# MoteinoM0CAM-M8.net
KiCad netlist of a schematic drawn in EAGLE
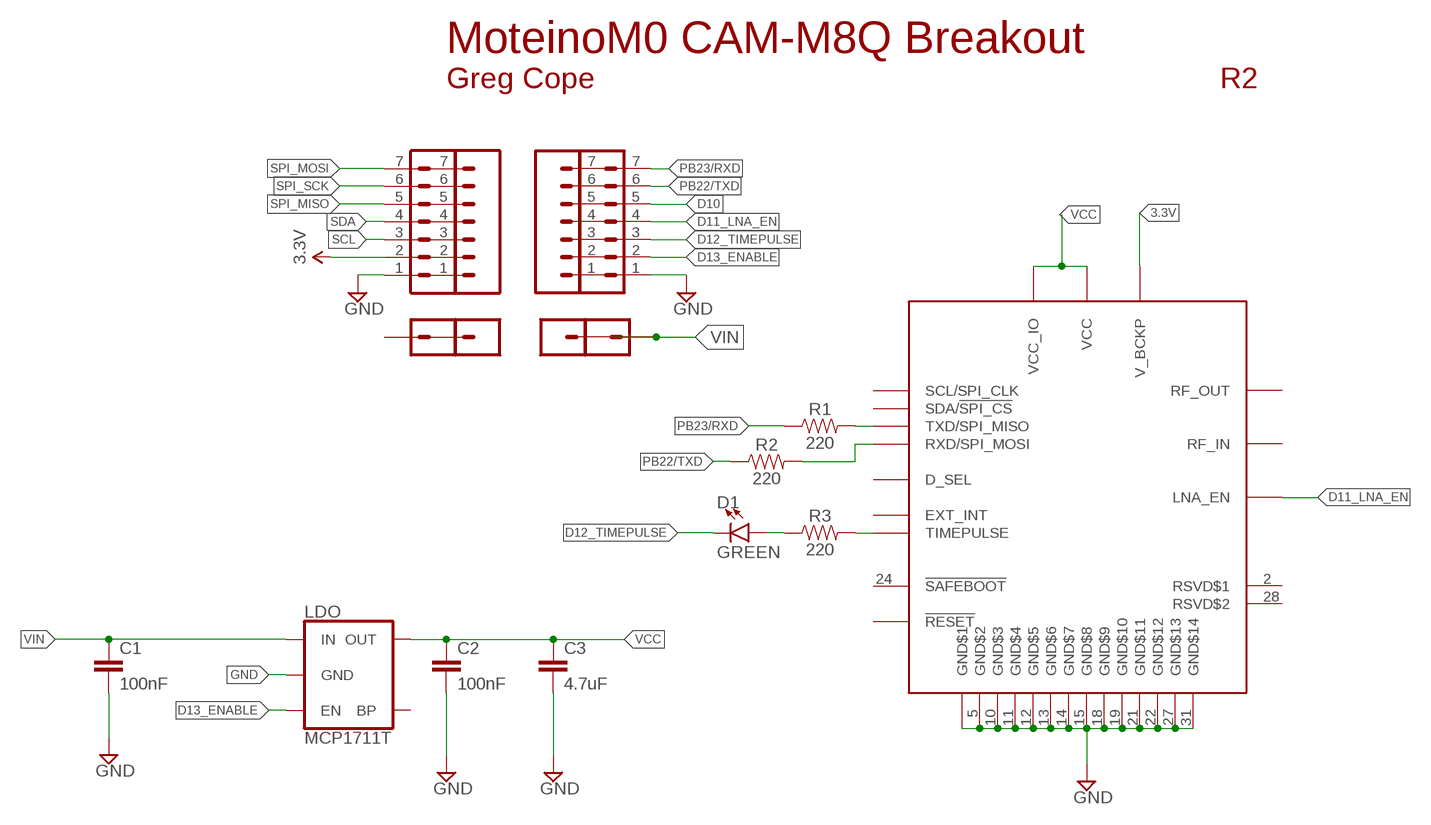
[diagram p0: schematic, sheet 1]

(export (version "E")
  (design (tool "Eeschema 10.0.6"))
  (components
    (comp (ref "C1")
      (value "100nF")
      (footprint "eagle-import:0603")
      (libsource (lib "eagle-import") (part "0.1UF-0603-25V-5%"))
    )
    (comp (ref "C2")
      (value "100nF")
      (footprint "eagle-import:0603")
      (libsource (lib "eagle-import") (part "0.1UF-0603-25V-5%"))
    )
    (comp (ref "C3")
      (value "4.7uF")
      (footprint "eagle-import:0603")
      (libsource (lib "eagle-import") (part "4.7UF0603"))
    )
    (comp (ref "D1")
      (value "GREEN")
      (footprint "eagle-import:LED-0603")
      (libsource (lib "eagle-import") (part "LED-GREEN0603"))
    )
    (comp (ref "J1")
      (value "CONN_01")
      (footprint "eagle-import:1X01")
      (libsource (lib "eagle-import") (part "CONN_01"))
    )
    (comp (ref "J2")
      (value "CONN_01")
      (footprint "eagle-import:1X01")
      (libsource (lib "eagle-import") (part "CONN_01"))
    )
    (comp (ref "J3")
      (value "CONN_01")
      (footprint "eagle-import:1X01")
      (libsource (lib "eagle-import") (part "CONN_01"))
    )
    (comp (ref "J4")
      (value "CONN_01")
      (footprint "eagle-import:1X01")
      (libsource (lib "eagle-import") (part "CONN_01"))
    )
    (comp (ref "LDO")
      (value "MCP1711T")
      (footprint "eagle-import:SOT23-5")
      (libsource (lib "eagle-import") (part "V_REG_SPX3819-SOT23-5"))
    )
    (comp (ref "R1")
      (value "220")
      (footprint "eagle-import:0603")
      (libsource (lib "eagle-import") (part "220OHM-0603-1/10W-1%"))
    )
    (comp (ref "R2")
      (value "220")
      (footprint "eagle-import:0603")
      (libsource (lib "eagle-import") (part "220OHM-0603-1/10W-1%"))
    )
    (comp (ref "R3")
      (value "220")
      (footprint "eagle-import:0603")
      (libsource (lib "eagle-import") (part "220OHM-0603-1/10W-1%"))
    )
    (comp (ref "U$1")
      (value "CAM-M8")
      (footprint "eagle-import:CAM-M8")
      (libsource (lib "eagle-import") (part "CAM-M8"))
    )
    (comp (ref "U$4")
      (value "HDR_7PINNS_THINRINGS")
      (footprint "eagle-import:1X07_NS_THINRINGS")
      (libsource (lib "eagle-import") (part "HDR_7PINNS_THINRINGS"))
    )
    (comp (ref "U$10")
      (value "HDR_7PINNS_THINRINGS")
      (footprint "eagle-import:1X07_NS_THINRINGS")
      (libsource (lib "eagle-import") (part "HDR_7PINNS_THINRINGS"))
    )
    (comp (ref "U$17")
      (value "HDR_7PINHH")
      (footprint "eagle-import:1X07_NS_THINRINGS_HH")
      (libsource (lib "eagle-import") (part "HDR_7PINHH"))
    )
    (comp (ref "U$18")
      (value "HDR_7PINHH")
      (footprint "eagle-import:1X07_NS_THINRINGS_HH")
      (libsource (lib "eagle-import") (part "HDR_7PINHH"))
    )
  )
  (nets
    (net (code "1") (name "3.3V") (class "Default")
      (node (ref "U$1") (pin "8") (pinfunction "V_BCKP_8") (pintype "power_in"))
      (node (ref "U$18") (pin "2") (pinfunction "2_2") (pintype "passive"))
    )
    (net (code "2") (name "D10") (class "Default")
      (node (ref "U$17") (pin "5") (pinfunction "5_5") (pintype "passive"))
    )
    (net (code "3") (name "D11_LNA_EN") (class "Default")
      (node (ref "U$1") (pin "30") (pinfunction "LNA_EN_30") (pintype "output"))
      (node (ref "U$17") (pin "4") (pinfunction "4_4") (pintype "passive"))
    )
    (net (code "4") (name "D12_TIMEPULSE") (class "Default")
      (node (ref "D1") (pin "C") (pinfunction "C_C") (pintype "passive"))
      (node (ref "U$17") (pin "3") (pinfunction "3_3") (pintype "passive"))
    )
    (net (code "5") (name "D13_ENABLE") (class "Default")
      (node (ref "LDO") (pin "3") (pinfunction "EN_3") (pintype "input"))
      (node (ref "U$17") (pin "2") (pinfunction "2_2") (pintype "passive"))
    )
    (net (code "6") (name "GND") (class "Default")
      (node (ref "C1") (pin "2") (pinfunction "2_2") (pintype "passive"))
      (node (ref "C2") (pin "2") (pinfunction "2_2") (pintype "passive"))
      (node (ref "C3") (pin "2") (pinfunction "2_2") (pintype "passive"))
      (node (ref "LDO") (pin "2") (pinfunction "GND_2") (pintype "input"))
      (node (ref "U$1") (pin "10") (pinfunction "GND$3_10") (pintype "power_in"))
      (node (ref "U$1") (pin "11") (pinfunction "GND$4_11") (pintype "power_in"))
      (node (ref "U$1") (pin "12") (pinfunction "GND$5_12") (pintype "power_in"))
      (node (ref "U$1") (pin "13") (pinfunction "GND$6_13") (pintype "power_in"))
      (node (ref "U$1") (pin "14") (pinfunction "GND$7_14") (pintype "power_in"))
      (node (ref "U$1") (pin "15") (pinfunction "GND$8_15") (pintype "power_in"))
      (node (ref "U$1") (pin "18") (pinfunction "GND$9_18") (pintype "power_in"))
      (node (ref "U$1") (pin "19") (pinfunction "GND$10_19") (pintype "power_in"))
      (node (ref "U$1") (pin "21") (pinfunction "GND$11_21") (pintype "power_in"))
      (node (ref "U$1") (pin "22") (pinfunction "GND$12_22") (pintype "power_in"))
      (node (ref "U$1") (pin "27") (pinfunction "GND$13_27") (pintype "power_in"))
      (node (ref "U$1") (pin "31") (pinfunction "GND$14_31") (pintype "power_in"))
      (node (ref "U$1") (pin "4") (pinfunction "GND$1_4") (pintype "power_in"))
      (node (ref "U$1") (pin "5") (pinfunction "GND$2_5") (pintype "power_in"))
      (node (ref "U$17") (pin "1") (pinfunction "1_1") (pintype "passive"))
      (node (ref "U$18") (pin "1") (pinfunction "1_1") (pintype "passive"))
    )
    (net (code "7") (name "Net-(D1-PadA)") (class "Default")
      (node (ref "D1") (pin "A") (pinfunction "A_A") (pintype "passive"))
      (node (ref "R3") (pin "1") (pinfunction "1_1") (pintype "passive"))
    )
    (net (code "8") (name "Net-(U$1-RXD{slash}SPI_MOSI)") (class "Default")
      (node (ref "R2") (pin "2") (pinfunction "2_2") (pintype "passive"))
      (node (ref "U$1") (pin "26") (pinfunction "RXD/SPI_MOSI_26") (pintype "input"))
    )
    (net (code "9") (name "Net-(U$1-TIMEPULSE)") (class "Default")
      (node (ref "R3") (pin "2") (pinfunction "2_2") (pintype "passive"))
      (node (ref "U$1") (pin "29") (pinfunction "TIMEPULSE_29") (pintype "output"))
    )
    (net (code "10") (name "Net-(U$1-TXD{slash}SPI_MISO)") (class "Default")
      (node (ref "R1") (pin "2") (pinfunction "2_2") (pintype "passive"))
      (node (ref "U$1") (pin "25") (pinfunction "TXD/SPI_MISO_25") (pintype "output"))
    )
    (net (code "11") (name "PB22{slash}TXD") (class "Default")
      (node (ref "R2") (pin "1") (pinfunction "1_1") (pintype "passive"))
      (node (ref "U$17") (pin "6") (pinfunction "6_6") (pintype "passive"))
    )
    (net (code "12") (name "PB23{slash}RXD") (class "Default")
      (node (ref "R1") (pin "1") (pinfunction "1_1") (pintype "passive"))
      (node (ref "U$17") (pin "7") (pinfunction "7_7") (pintype "passive"))
    )
    (net (code "13") (name "SCL") (class "Default")
      (node (ref "U$18") (pin "3") (pinfunction "3_3") (pintype "passive"))
    )
    (net (code "14") (name "SDA") (class "Default")
      (node (ref "U$18") (pin "4") (pinfunction "4_4") (pintype "passive"))
    )
    (net (code "15") (name "SPI_MISO") (class "Default")
      (node (ref "U$18") (pin "5") (pinfunction "5_5") (pintype "passive"))
    )
    (net (code "16") (name "SPI_MOSI") (class "Default")
      (node (ref "U$18") (pin "7") (pinfunction "7_7") (pintype "passive"))
    )
    (net (code "17") (name "SPI_SCK") (class "Default")
      (node (ref "U$18") (pin "6") (pinfunction "6_6") (pintype "passive"))
    )
    (net (code "18") (name "VCC") (class "Default")
      (node (ref "C2") (pin "1") (pinfunction "1_1") (pintype "passive"))
      (node (ref "C3") (pin "1") (pinfunction "1_1") (pintype "passive"))
      (node (ref "LDO") (pin "5") (pinfunction "OUT_5") (pintype "passive"))
      (node (ref "U$1") (pin "1") (pinfunction "VCC_IO_1") (pintype "power_in"))
      (node (ref "U$1") (pin "9") (pinfunction "VCC_9") (pintype "power_in"))
    )
    (net (code "19") (name "VIN") (class "Default")
      (node (ref "C1") (pin "1") (pinfunction "1_1") (pintype "passive"))
      (node (ref "J3") (pin "1") (pinfunction "1_1") (pintype "passive"))
      (node (ref "J4") (pin "1") (pinfunction "1_1") (pintype "passive"))
      (node (ref "LDO") (pin "1") (pinfunction "IN_1") (pintype "input"))
    )
    (net (code "20") (name "unconnected-(J1-Pad1)") (class "Default")
      (node (ref "J1") (pin "1") (pinfunction "1_1") (pintype "passive"))
    )
    (net (code "21") (name "unconnected-(J2-Pad1)") (class "Default")
      (node (ref "J2") (pin "1") (pinfunction "1_1") (pintype "passive"))
    )
    (net (code "22") (name "unconnected-(LDO-BP-Pad4)") (class "Default")
      (node (ref "LDO") (pin "4") (pinfunction "BP_4") (pintype "input"))
    )
    (net (code "23") (name "unconnected-(U$1-D_SEL-Pad20)") (class "Default")
      (node (ref "U$1") (pin "20") (pinfunction "D_SEL_20") (pintype "input"))
    )
    (net (code "24") (name "unconnected-(U$1-EXT_INT-Pad7)") (class "Default")
      (node (ref "U$1") (pin "7") (pinfunction "EXT_INT_7") (pintype "bidirectional"))
    )
    (net (code "25") (name "unconnected-(U$1-RF_IN-Pad17)") (class "Default")
      (node (ref "U$1") (pin "17") (pinfunction "RF_IN_17") (pintype "input"))
    )
    (net (code "26") (name "unconnected-(U$1-RF_OUT-Pad16)") (class "Default")
      (node (ref "U$1") (pin "16") (pinfunction "RF_OUT_16") (pintype "output"))
    )
    (net (code "27") (name "unconnected-(U$1-RSVD$1-Pad2)") (class "Default")
      (node (ref "U$1") (pin "2") (pinfunction "RSVD$1_2") (pintype "no_connect"))
    )
    (net (code "28") (name "unconnected-(U$1-RSVD$2-Pad28)") (class "Default")
      (node (ref "U$1") (pin "28") (pinfunction "RSVD$2_28") (pintype "no_connect"))
    )
    (net (code "29") (name "unconnected-(U$1-SCL{slash}SPI_CLK-Pad6)") (class "Default")
      (node (ref "U$1") (pin "6") (pinfunction "SCL/SPI_CLK_6") (pintype "input"))
    )
    (net (code "30") (name "unconnected-(U$1-SDA{slash}~{SPI_CS}-Pad3)") (class "Default")
      (node (ref "U$1") (pin "3") (pinfunction "SDA/~{SPI_CS}_3") (pintype "bidirectional"))
    )
    (net (code "31") (name "unconnected-(U$1-~{RESET}-Pad23)") (class "Default")
      (node (ref "U$1") (pin "23") (pinfunction "~{RESET}_23") (pintype "input"))
    )
    (net (code "32") (name "unconnected-(U$1-~{SAFEBOOT}-Pad24)") (class "Default")
      (node (ref "U$1") (pin "24") (pinfunction "~{SAFEBOOT}_24") (pintype "input"))
    )
    (net (code "33") (name "unconnected-(U$4-Pad1)") (class "Default")
      (node (ref "U$4") (pin "1") (pinfunction "1_1") (pintype "passive"))
    )
    (net (code "34") (name "unconnected-(U$4-Pad2)") (class "Default")
      (node (ref "U$4") (pin "2") (pinfunction "2_2") (pintype "passive"))
    )
    (net (code "35") (name "unconnected-(U$4-Pad3)") (class "Default")
      (node (ref "U$4") (pin "3") (pinfunction "3_3") (pintype "passive"))
    )
    (net (code "36") (name "unconnected-(U$4-Pad4)") (class "Default")
      (node (ref "U$4") (pin "4") (pinfunction "4_4") (pintype "passive"))
    )
    (net (code "37") (name "unconnected-(U$4-Pad5)") (class "Default")
      (node (ref "U$4") (pin "5") (pinfunction "5_5") (pintype "passive"))
    )
    (net (code "38") (name "unconnected-(U$4-Pad6)") (class "Default")
      (node (ref "U$4") (pin "6") (pinfunction "6_6") (pintype "passive"))
    )
    (net (code "39") (name "unconnected-(U$4-Pad7)") (class "Default")
      (node (ref "U$4") (pin "7") (pinfunction "7_7") (pintype "passive"))
    )
    (net (code "40") (name "unconnected-(U$10-Pad1)") (class "Default")
      (node (ref "U$10") (pin "1") (pinfunction "1_1") (pintype "passive"))
    )
    (net (code "41") (name "unconnected-(U$10-Pad2)") (class "Default")
      (node (ref "U$10") (pin "2") (pinfunction "2_2") (pintype "passive"))
    )
    (net (code "42") (name "unconnected-(U$10-Pad3)") (class "Default")
      (node (ref "U$10") (pin "3") (pinfunction "3_3") (pintype "passive"))
    )
    (net (code "43") (name "unconnected-(U$10-Pad4)") (class "Default")
      (node (ref "U$10") (pin "4") (pinfunction "4_4") (pintype "passive"))
    )
    (net (code "44") (name "unconnected-(U$10-Pad5)") (class "Default")
      (node (ref "U$10") (pin "5") (pinfunction "5_5") (pintype "passive"))
    )
    (net (code "45") (name "unconnected-(U$10-Pad6)") (class "Default")
      (node (ref "U$10") (pin "6") (pinfunction "6_6") (pintype "passive"))
    )
    (net (code "46") (name "unconnected-(U$10-Pad7)") (class "Default")
      (node (ref "U$10") (pin "7") (pinfunction "7_7") (pintype "passive"))
    )
  )
)
